# CHANNEL_DELAY.net
KiCad netlist of a schematic drawn in Altium Designer
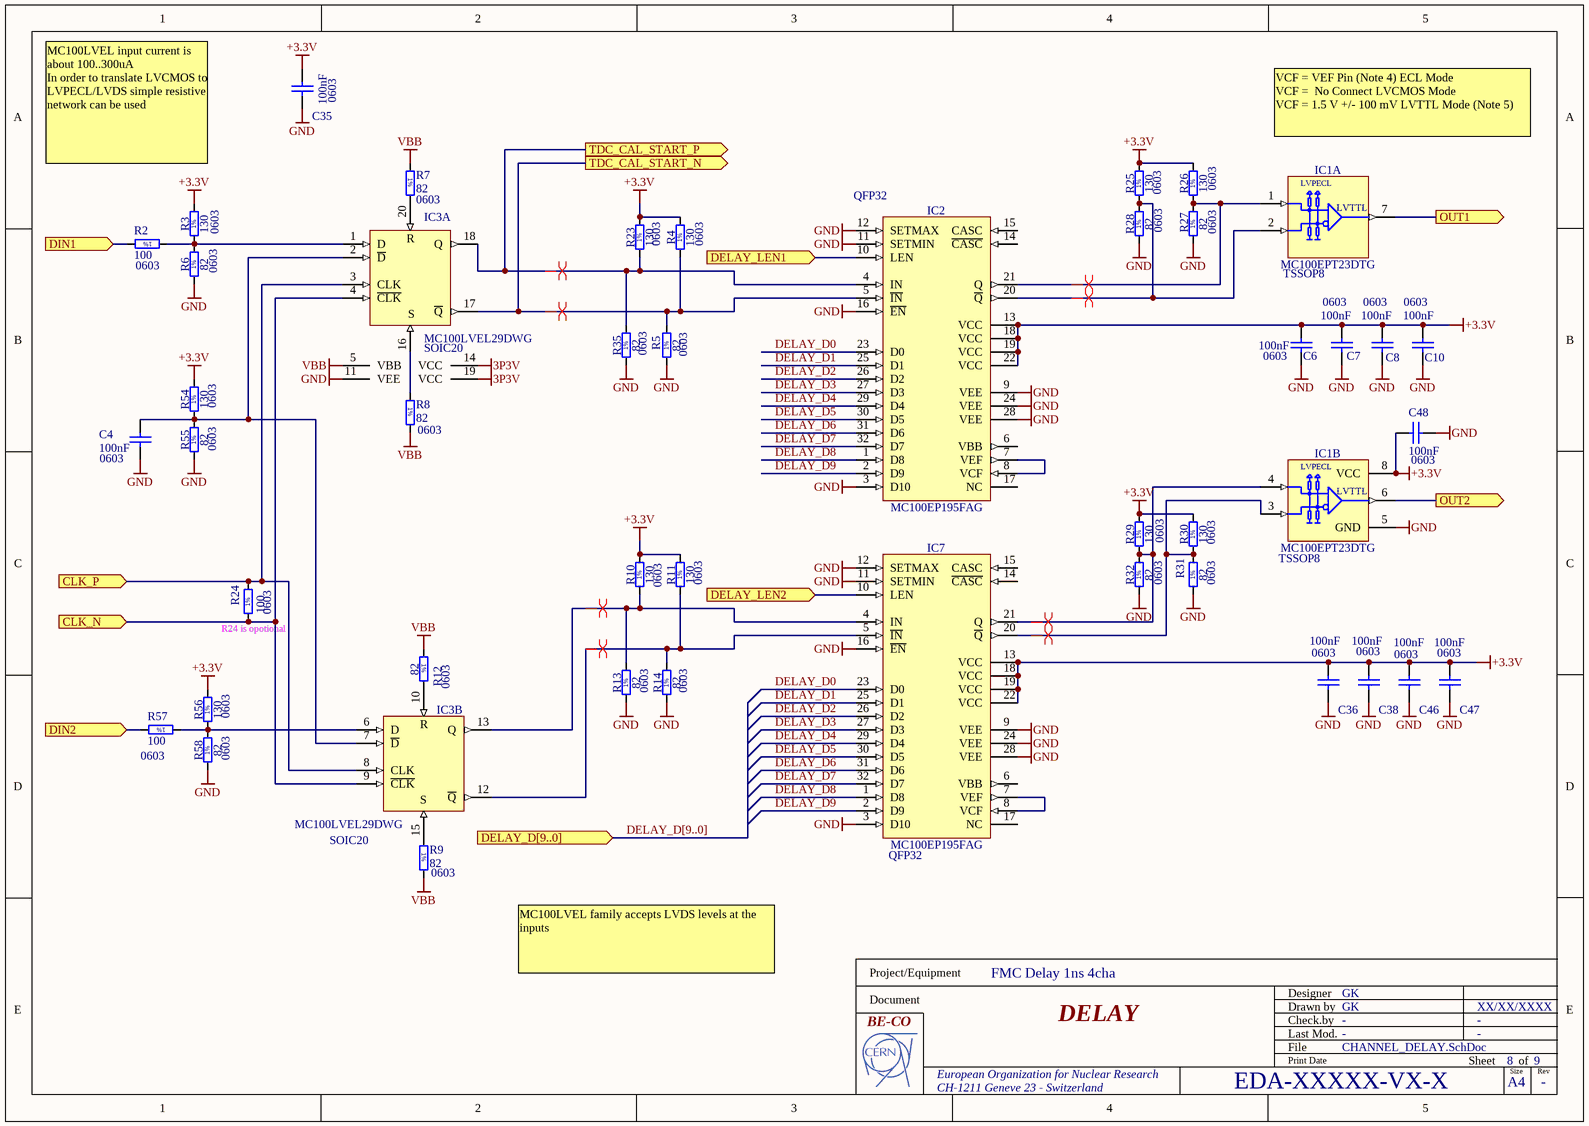
[diagram p0: CHANNEL_DELAY.SchDoc]

(export (version "E")
  (design (tool "Eeschema 10.0.6"))
  (components
    (comp (ref "C4")
      (value "100nF")
      (footprint "CAPC1608X87N")
      (description "Non-polarised capacitor")
      (fields
        (field (name "CASE") "0603")
        (field (name "MANUFACTURER1 PART NUMBER") "223858615649")
        (field (name "MANUFACTURER") "GENERIC")
        (field (name "AUTHOR") "CERN DEM JLC")
      )
      (libsource (lib "Capacitors") (part "Capacitor - non polarized"))
    )
    (comp (ref "C6")
      (value "100nF")
      (footprint "CAPC1608X87N")
      (description "Non-polarised capacitor")
      (fields
        (field (name "CASE") "0603")
        (field (name "MANUFACTURER1 PART NUMBER") "223858615649")
        (field (name "MANUFACTURER") "GENERIC")
        (field (name "AUTHOR") "CERN DEM JLC")
      )
      (libsource (lib "Capacitors") (part "Capacitor - non polarized"))
    )
    (comp (ref "C7")
      (value "100nF")
      (footprint "CAPC1608X87N")
      (description "Non-polarised capacitor")
      (fields
        (field (name "CASE") "0603")
        (field (name "MANUFACTURER1 PART NUMBER") "223858615649")
        (field (name "MANUFACTURER") "GENERIC")
        (field (name "AUTHOR") "CERN DEM JLC")
      )
      (libsource (lib "Capacitors") (part "Capacitor - non polarized"))
    )
    (comp (ref "C8")
      (value "100nF")
      (footprint "CAPC1608X87N")
      (description "Non-polarised capacitor")
      (fields
        (field (name "CASE") "0603")
        (field (name "MANUFACTURER1 PART NUMBER") "223858615649")
        (field (name "MANUFACTURER") "GENERIC")
        (field (name "AUTHOR") "CERN DEM JLC")
      )
      (libsource (lib "Capacitors") (part "Capacitor - non polarized"))
    )
    (comp (ref "C10")
      (value "100nF")
      (footprint "CAPC1608X87N")
      (description "Non-polarised capacitor")
      (fields
        (field (name "CASE") "0603")
        (field (name "MANUFACTURER1 PART NUMBER") "223858615649")
        (field (name "MANUFACTURER") "GENERIC")
        (field (name "AUTHOR") "CERN DEM JLC")
      )
      (libsource (lib "Capacitors") (part "Capacitor - non polarized"))
    )
    (comp (ref "C35")
      (value "100nF")
      (footprint "CAPC1608X87N")
      (description "Non-polarised capacitor")
      (fields
        (field (name "CASE") "0603")
        (field (name "MANUFACTURER1 PART NUMBER") "223858615649")
        (field (name "MANUFACTURER") "GENERIC")
        (field (name "AUTHOR") "CERN DEM JLC")
      )
      (libsource (lib "Capacitors") (part "Capacitor - non polarized"))
    )
    (comp (ref "C36")
      (value "100nF")
      (footprint "CAPC1608X87N")
      (description "Non-polarised capacitor")
      (fields
        (field (name "CASE") "0603")
        (field (name "MANUFACTURER1 PART NUMBER") "223858615649")
        (field (name "MANUFACTURER") "GENERIC")
        (field (name "AUTHOR") "CERN DEM JLC")
      )
      (libsource (lib "Capacitors") (part "Capacitor - non polarized"))
    )
    (comp (ref "C38")
      (value "100nF")
      (footprint "CAPC1608X87N")
      (description "Non-polarised capacitor")
      (fields
        (field (name "CASE") "0603")
        (field (name "MANUFACTURER1 PART NUMBER") "223858615649")
        (field (name "MANUFACTURER") "GENERIC")
        (field (name "AUTHOR") "CERN DEM JLC")
      )
      (libsource (lib "Capacitors") (part "Capacitor - non polarized"))
    )
    (comp (ref "C46")
      (value "100nF")
      (footprint "CAPC1608X87N")
      (description "Non-polarised capacitor")
      (fields
        (field (name "CASE") "0603")
        (field (name "MANUFACTURER1 PART NUMBER") "223858615649")
        (field (name "MANUFACTURER") "GENERIC")
        (field (name "AUTHOR") "CERN DEM JLC")
      )
      (libsource (lib "Capacitors") (part "Capacitor - non polarized"))
    )
    (comp (ref "C47")
      (value "100nF")
      (footprint "CAPC1608X87N")
      (description "Non-polarised capacitor")
      (fields
        (field (name "CASE") "0603")
        (field (name "MANUFACTURER1 PART NUMBER") "223858615649")
        (field (name "MANUFACTURER") "GENERIC")
        (field (name "AUTHOR") "CERN DEM JLC")
      )
      (libsource (lib "Capacitors") (part "Capacitor - non polarized"))
    )
    (comp (ref "C48")
      (value "100nF")
      (footprint "CAPC1608X87N")
      (description "Non-polarised capacitor")
      (fields
        (field (name "CASE") "0603")
        (field (name "MANUFACTURER1 PART NUMBER") "223858615649")
        (field (name "MANUFACTURER") "GENERIC")
        (field (name "AUTHOR") "CERN DEM JLC")
      )
      (libsource (lib "Capacitors") (part "Capacitor - non polarized"))
    )
    (comp (ref "IC1")
      (value "MC100EPT23DTG")
      (footprint "SOP65P490X110-8N")
      (description "3.3V Dual Differential LVPECL/LVDS/CML  to LVTTL/LVCMOS Translator")
      (fields
        (field (name "MANUFACTURER") "ON SEMICONDUCTOR")
        (field (name "CASE") "TSSOP8")
        (field (name "AUTHOR") "CERN DEM JLC")
      )
      (libsource (lib "ICs And Semiconductors") (part "100EPT23D"))
    )
    (comp (ref "IC2")
      (value "MC100EP195FAG")
      (footprint "QFP80P900X900X160-32AN")
      (description "3.3V ECL Programmable Delay Chip")
      (fields
        (field (name "PART NUMBER") "MC100EP195BFAG")
        (field (name "MANUFACTURER") "ON SEMICONDUCTOR")
        (field (name "CASE") "QFP32")
        (field (name "AUTHOR") "CERN DEM JLC")
      )
      (libsource (lib "ICs And Semiconductors") (part "MC100EP195FA"))
    )
    (comp (ref "IC3")
      (value "MC100LVEL29DWG")
      (footprint "SOIC127P1030X265-20N")
      (description "3.3V ECL Dual Differential Data and Clock D Flip-Flop With Set and Reset")
      (fields
        (field (name "MANUFACTURER") "ON SEMICONDUCTOR")
        (field (name "CASE") "SOIC20")
        (field (name "AUTHOR") "CERN DEM JLC")
      )
      (libsource (lib "ICs And Semiconductors") (part "100LVEL29"))
    )
    (comp (ref "IC7")
      (value "MC100EP195FAG")
      (footprint "QFP80P900X900X160-32AN")
      (description "3.3V ECL Programmable Delay Chip")
      (fields
        (field (name "PART NUMBER") "MC100EP195BFAG")
        (field (name "MANUFACTURER") "ON SEMICONDUCTOR")
        (field (name "CASE") "QFP32")
        (field (name "AUTHOR") "CERN DEM JLC")
      )
      (libsource (lib "ICs And Semiconductors") (part "MC100EP195FA"))
    )
    (comp (ref "R2")
      (value "100")
      (footprint "RESC1608X55N")
      (description "Resistor - 1%")
      (fields
        (field (name "PART NUMBER") "R0603_100R_1%_0.1W_100PPM")
        (field (name "POWER") "0.1W")
        (field (name "CASE") "0603")
        (field (name "AUTHOR") "CERN DEM JLC")
      )
      (libsource (lib "Resistors") (part "Resistor - 1%"))
    )
    (comp (ref "R3")
      (value "130")
      (footprint "RESC1608X55N")
      (description "Resistor - 1%")
      (fields
        (field (name "PART NUMBER") "R0603_130R_1%_0.1W_100PPM")
        (field (name "POWER") "0.1W")
        (field (name "CASE") "0603")
        (field (name "AUTHOR") "CERN DEM JLC")
      )
      (libsource (lib "Resistors") (part "Resistor - 1%"))
    )
    (comp (ref "R4")
      (value "130")
      (footprint "RESC1608X55N")
      (description "Resistor - 1%")
      (fields
        (field (name "PART NUMBER") "R0603_130R_1%_0.1W_100PPM")
        (field (name "POWER") "0.1W")
        (field (name "CASE") "0603")
        (field (name "AUTHOR") "CERN DEM JLC")
      )
      (libsource (lib "Resistors") (part "Resistor - 1%"))
    )
    (comp (ref "R5")
      (value "82")
      (footprint "RESC1608X55N")
      (description "Resistor - 1%")
      (fields
        (field (name "PART NUMBER") "R0603_82R_1%_0.1W_100PPM")
        (field (name "POWER") "0.1W")
        (field (name "CASE") "0603")
        (field (name "AUTHOR") "CERN DEM JLC")
      )
      (libsource (lib "Resistors") (part "Resistor - 1%"))
    )
    (comp (ref "R6")
      (value "82")
      (footprint "RESC1608X55N")
      (description "Resistor - 1%")
      (fields
        (field (name "PART NUMBER") "R0603_82R_1%_0.1W_100PPM")
        (field (name "POWER") "0.1W")
        (field (name "CASE") "0603")
        (field (name "AUTHOR") "CERN DEM JLC")
      )
      (libsource (lib "Resistors") (part "Resistor - 1%"))
    )
    (comp (ref "R7")
      (value "82")
      (footprint "RESC1608X55N")
      (description "Resistor - 1%")
      (fields
        (field (name "PART NUMBER") "R0603_82R_1%_0.1W_100PPM")
        (field (name "POWER") "0.1W")
        (field (name "CASE") "0603")
        (field (name "AUTHOR") "CERN DEM JLC")
      )
      (libsource (lib "Resistors") (part "Resistor - 1%"))
    )
    (comp (ref "R8")
      (value "82")
      (footprint "RESC1608X55N")
      (description "Resistor - 1%")
      (fields
        (field (name "PART NUMBER") "R0603_82R_1%_0.1W_100PPM")
        (field (name "POWER") "0.1W")
        (field (name "CASE") "0603")
        (field (name "AUTHOR") "CERN DEM JLC")
      )
      (libsource (lib "Resistors") (part "Resistor - 1%"))
    )
    (comp (ref "R9")
      (value "82")
      (footprint "RESC1608X55N")
      (description "Resistor - 1%")
      (fields
        (field (name "PART NUMBER") "R0603_82R_1%_0.1W_100PPM")
        (field (name "POWER") "0.1W")
        (field (name "CASE") "0603")
        (field (name "AUTHOR") "CERN DEM JLC")
      )
      (libsource (lib "Resistors") (part "Resistor - 1%"))
    )
    (comp (ref "R10")
      (value "130")
      (footprint "RESC1608X55N")
      (description "Resistor - 1%")
      (fields
        (field (name "PART NUMBER") "R0603_130R_1%_0.1W_100PPM")
        (field (name "POWER") "0.1W")
        (field (name "CASE") "0603")
        (field (name "AUTHOR") "CERN DEM JLC")
      )
      (libsource (lib "Resistors") (part "Resistor - 1%"))
    )
    (comp (ref "R11")
      (value "130")
      (footprint "RESC1608X55N")
      (description "Resistor - 1%")
      (fields
        (field (name "PART NUMBER") "R0603_130R_1%_0.1W_100PPM")
        (field (name "POWER") "0.1W")
        (field (name "CASE") "0603")
        (field (name "AUTHOR") "CERN DEM JLC")
      )
      (libsource (lib "Resistors") (part "Resistor - 1%"))
    )
    (comp (ref "R12")
      (value "82")
      (footprint "RESC1608X55N")
      (description "Resistor - 1%")
      (fields
        (field (name "PART NUMBER") "R0603_82R_1%_0.1W_100PPM")
        (field (name "POWER") "0.1W")
        (field (name "CASE") "0603")
        (field (name "AUTHOR") "CERN DEM JLC")
      )
      (libsource (lib "Resistors") (part "Resistor - 1%"))
    )
    (comp (ref "R13")
      (value "82")
      (footprint "RESC1608X55N")
      (description "Resistor - 1%")
      (fields
        (field (name "PART NUMBER") "R0603_82R_1%_0.1W_100PPM")
        (field (name "POWER") "0.1W")
        (field (name "CASE") "0603")
        (field (name "AUTHOR") "CERN DEM JLC")
      )
      (libsource (lib "Resistors") (part "Resistor - 1%"))
    )
    (comp (ref "R14")
      (value "82")
      (footprint "RESC1608X55N")
      (description "Resistor - 1%")
      (fields
        (field (name "PART NUMBER") "R0603_82R_1%_0.1W_100PPM")
        (field (name "POWER") "0.1W")
        (field (name "CASE") "0603")
        (field (name "AUTHOR") "CERN DEM JLC")
      )
      (libsource (lib "Resistors") (part "Resistor - 1%"))
    )
    (comp (ref "R23")
      (value "130")
      (footprint "RESC1608X55N")
      (description "Resistor - 1%")
      (fields
        (field (name "PART NUMBER") "R0603_130R_1%_0.1W_100PPM")
        (field (name "POWER") "0.1W")
        (field (name "CASE") "0603")
        (field (name "AUTHOR") "CERN DEM JLC")
      )
      (libsource (lib "Resistors") (part "Resistor - 1%"))
    )
    (comp (ref "R24")
      (value "100")
      (footprint "RESC1608X55N")
      (description "Resistor - 1%")
      (fields
        (field (name "PART NUMBER") "R0603_100R_1%_0.1W_100PPM")
        (field (name "POWER") "0.1W")
        (field (name "CASE") "0603")
        (field (name "AUTHOR") "CERN DEM JLC")
      )
      (libsource (lib "Resistors") (part "Resistor - 1%"))
    )
    (comp (ref "R25")
      (value "130")
      (footprint "RESC1608X55N")
      (description "Resistor - 1%")
      (fields
        (field (name "PART NUMBER") "R0603_130R_1%_0.1W_100PPM")
        (field (name "POWER") "0.1W")
        (field (name "CASE") "0603")
        (field (name "AUTHOR") "CERN DEM JLC")
      )
      (libsource (lib "Resistors") (part "Resistor - 1%"))
    )
    (comp (ref "R26")
      (value "130")
      (footprint "RESC1608X55N")
      (description "Resistor - 1%")
      (fields
        (field (name "PART NUMBER") "R0603_130R_1%_0.1W_100PPM")
        (field (name "POWER") "0.1W")
        (field (name "CASE") "0603")
        (field (name "AUTHOR") "CERN DEM JLC")
      )
      (libsource (lib "Resistors") (part "Resistor - 1%"))
    )
    (comp (ref "R27")
      (value "82")
      (footprint "RESC1608X55N")
      (description "Resistor - 1%")
      (fields
        (field (name "PART NUMBER") "R0603_82R_1%_0.1W_100PPM")
        (field (name "POWER") "0.1W")
        (field (name "CASE") "0603")
        (field (name "AUTHOR") "CERN DEM JLC")
      )
      (libsource (lib "Resistors") (part "Resistor - 1%"))
    )
    (comp (ref "R28")
      (value "82")
      (footprint "RESC1608X55N")
      (description "Resistor - 1%")
      (fields
        (field (name "PART NUMBER") "R0603_82R_1%_0.1W_100PPM")
        (field (name "POWER") "0.1W")
        (field (name "CASE") "0603")
        (field (name "AUTHOR") "CERN DEM JLC")
      )
      (libsource (lib "Resistors") (part "Resistor - 1%"))
    )
    (comp (ref "R29")
      (value "130")
      (footprint "RESC1608X55N")
      (description "Resistor - 1%")
      (fields
        (field (name "PART NUMBER") "R0603_130R_1%_0.1W_100PPM")
        (field (name "POWER") "0.1W")
        (field (name "CASE") "0603")
        (field (name "AUTHOR") "CERN DEM JLC")
      )
      (libsource (lib "Resistors") (part "Resistor - 1%"))
    )
    (comp (ref "R30")
      (value "130")
      (footprint "RESC1608X55N")
      (description "Resistor - 1%")
      (fields
        (field (name "PART NUMBER") "R0603_130R_1%_0.1W_100PPM")
        (field (name "POWER") "0.1W")
        (field (name "CASE") "0603")
        (field (name "AUTHOR") "CERN DEM JLC")
      )
      (libsource (lib "Resistors") (part "Resistor - 1%"))
    )
    (comp (ref "R31")
      (value "82")
      (footprint "RESC1608X55N")
      (description "Resistor - 1%")
      (fields
        (field (name "PART NUMBER") "R0603_82R_1%_0.1W_100PPM")
        (field (name "POWER") "0.1W")
        (field (name "CASE") "0603")
        (field (name "AUTHOR") "CERN DEM JLC")
      )
      (libsource (lib "Resistors") (part "Resistor - 1%"))
    )
    (comp (ref "R32")
      (value "82")
      (footprint "RESC1608X55N")
      (description "Resistor - 1%")
      (fields
        (field (name "PART NUMBER") "R0603_82R_1%_0.1W_100PPM")
        (field (name "POWER") "0.1W")
        (field (name "CASE") "0603")
        (field (name "AUTHOR") "CERN DEM JLC")
      )
      (libsource (lib "Resistors") (part "Resistor - 1%"))
    )
    (comp (ref "R35")
      (value "82")
      (footprint "RESC1608X55N")
      (description "Resistor - 1%")
      (fields
        (field (name "PART NUMBER") "R0603_82R_1%_0.1W_100PPM")
        (field (name "POWER") "0.1W")
        (field (name "CASE") "0603")
        (field (name "AUTHOR") "CERN DEM JLC")
      )
      (libsource (lib "Resistors") (part "Resistor - 1%"))
    )
    (comp (ref "R54")
      (value "130")
      (footprint "RESC1608X55N")
      (description "Resistor - 1%")
      (fields
        (field (name "PART NUMBER") "R0603_130R_1%_0.1W_100PPM")
        (field (name "POWER") "0.1W")
        (field (name "CASE") "0603")
        (field (name "AUTHOR") "CERN DEM JLC")
      )
      (libsource (lib "Resistors") (part "Resistor - 1%"))
    )
    (comp (ref "R55")
      (value "82")
      (footprint "RESC1608X55N")
      (description "Resistor - 1%")
      (fields
        (field (name "PART NUMBER") "R0603_82R_1%_0.1W_100PPM")
        (field (name "POWER") "0.1W")
        (field (name "CASE") "0603")
        (field (name "AUTHOR") "CERN DEM JLC")
      )
      (libsource (lib "Resistors") (part "Resistor - 1%"))
    )
    (comp (ref "R56")
      (value "130")
      (footprint "RESC1608X55N")
      (description "Resistor - 1%")
      (fields
        (field (name "PART NUMBER") "R0603_130R_1%_0.1W_100PPM")
        (field (name "POWER") "0.1W")
        (field (name "CASE") "0603")
        (field (name "AUTHOR") "CERN DEM JLC")
      )
      (libsource (lib "Resistors") (part "Resistor - 1%"))
    )
    (comp (ref "R57")
      (value "100")
      (footprint "RESC1608X55N")
      (description "Resistor - 1%")
      (fields
        (field (name "PART NUMBER") "R0603_100R_1%_0.1W_100PPM")
        (field (name "POWER") "0.1W")
        (field (name "CASE") "0603")
        (field (name "AUTHOR") "CERN DEM JLC")
      )
      (libsource (lib "Resistors") (part "Resistor - 1%"))
    )
    (comp (ref "R58")
      (value "82")
      (footprint "RESC1608X55N")
      (description "Resistor - 1%")
      (fields
        (field (name "PART NUMBER") "R0603_82R_1%_0.1W_100PPM")
        (field (name "POWER") "0.1W")
        (field (name "CASE") "0603")
        (field (name "AUTHOR") "CERN DEM JLC")
      )
      (libsource (lib "Resistors") (part "Resistor - 1%"))
    )
  )
  (nets
    (net (code "1") (name "+3.3V") (class "Default")
      (node (ref "C10") (pin "1") (pinfunction "1_1") (pintype "passive"))
      (node (ref "C35") (pin "1") (pinfunction "1_1") (pintype "passive"))
      (node (ref "C36") (pin "1") (pinfunction "1_1") (pintype "passive"))
      (node (ref "C38") (pin "1") (pinfunction "1_1") (pintype "passive"))
      (node (ref "C46") (pin "1") (pinfunction "1_1") (pintype "passive"))
      (node (ref "C47") (pin "1") (pinfunction "1_1") (pintype "passive"))
      (node (ref "C48") (pin "1") (pinfunction "1_1") (pintype "passive"))
      (node (ref "C6") (pin "1") (pinfunction "1_1") (pintype "passive"))
      (node (ref "C7") (pin "1") (pinfunction "1_1") (pintype "passive"))
      (node (ref "C8") (pin "1") (pinfunction "1_1") (pintype "passive"))
      (node (ref "IC1") (pin "8") (pinfunction "VCC_8") (pintype "power_in"))
      (node (ref "IC2") (pin "13") (pinfunction "VCC_13") (pintype "power_in"))
      (node (ref "IC2") (pin "18") (pinfunction "VCC_18") (pintype "power_in"))
      (node (ref "IC2") (pin "19") (pinfunction "VCC_19") (pintype "power_in"))
      (node (ref "IC2") (pin "22") (pinfunction "VCC_22") (pintype "power_in"))
      (node (ref "IC3") (pin "14") (pinfunction "VCC_14") (pintype "power_in"))
      (node (ref "IC3") (pin "19") (pinfunction "VCC_19") (pintype "power_in"))
      (node (ref "IC7") (pin "13") (pinfunction "VCC_13") (pintype "power_in"))
      (node (ref "IC7") (pin "18") (pinfunction "VCC_18") (pintype "power_in"))
      (node (ref "IC7") (pin "19") (pinfunction "VCC_19") (pintype "power_in"))
      (node (ref "IC7") (pin "22") (pinfunction "VCC_22") (pintype "power_in"))
      (node (ref "R10") (pin "2") (pinfunction "2_2") (pintype "passive"))
      (node (ref "R11") (pin "2") (pinfunction "2_2") (pintype "passive"))
      (node (ref "R23") (pin "2") (pinfunction "2_2") (pintype "passive"))
      (node (ref "R25") (pin "2") (pinfunction "2_2") (pintype "passive"))
      (node (ref "R26") (pin "2") (pinfunction "2_2") (pintype "passive"))
      (node (ref "R29") (pin "2") (pinfunction "2_2") (pintype "passive"))
      (node (ref "R3") (pin "2") (pinfunction "2_2") (pintype "passive"))
      (node (ref "R30") (pin "2") (pinfunction "2_2") (pintype "passive"))
      (node (ref "R4") (pin "2") (pinfunction "2_2") (pintype "passive"))
      (node (ref "R54") (pin "2") (pinfunction "2_2") (pintype "passive"))
      (node (ref "R56") (pin "2") (pinfunction "2_2") (pintype "passive"))
    )
    (net (code "2") (name "/CLK_N") (class "Default")
      (node (ref "IC3") (pin "4") (pinfunction "~{CLK}_4") (pintype "input"))
      (node (ref "IC3") (pin "9") (pinfunction "~{CLK}_9") (pintype "input"))
      (node (ref "R24") (pin "1") (pinfunction "1_1") (pintype "passive"))
    )
    (net (code "3") (name "/CLK_P") (class "Default")
      (node (ref "IC3") (pin "3") (pinfunction "CLK_3") (pintype "input"))
      (node (ref "IC3") (pin "8") (pinfunction "CLK_8") (pintype "input"))
      (node (ref "R24") (pin "2") (pinfunction "2_2") (pintype "passive"))
    )
    (net (code "4") (name "/DELAY_D0") (class "Default")
      (node (ref "IC2") (pin "23") (pinfunction "D0_23") (pintype "input"))
      (node (ref "IC7") (pin "23") (pinfunction "D0_23") (pintype "input"))
    )
    (net (code "5") (name "/DELAY_D1") (class "Default")
      (node (ref "IC2") (pin "25") (pinfunction "D1_25") (pintype "input"))
      (node (ref "IC7") (pin "25") (pinfunction "D1_25") (pintype "input"))
    )
    (net (code "6") (name "/DELAY_D2") (class "Default")
      (node (ref "IC2") (pin "26") (pinfunction "D2_26") (pintype "input"))
      (node (ref "IC7") (pin "26") (pinfunction "D2_26") (pintype "input"))
    )
    (net (code "7") (name "/DELAY_D3") (class "Default")
      (node (ref "IC2") (pin "27") (pinfunction "D3_27") (pintype "input"))
      (node (ref "IC7") (pin "27") (pinfunction "D3_27") (pintype "input"))
    )
    (net (code "8") (name "/DELAY_D4") (class "Default")
      (node (ref "IC2") (pin "29") (pinfunction "D4_29") (pintype "input"))
      (node (ref "IC7") (pin "29") (pinfunction "D4_29") (pintype "input"))
    )
    (net (code "9") (name "/DELAY_D5") (class "Default")
      (node (ref "IC2") (pin "30") (pinfunction "D5_30") (pintype "input"))
      (node (ref "IC7") (pin "30") (pinfunction "D5_30") (pintype "input"))
    )
    (net (code "10") (name "/DELAY_D6") (class "Default")
      (node (ref "IC2") (pin "31") (pinfunction "D6_31") (pintype "input"))
      (node (ref "IC7") (pin "31") (pinfunction "D6_31") (pintype "input"))
    )
    (net (code "11") (name "/DELAY_D7") (class "Default")
      (node (ref "IC2") (pin "32") (pinfunction "D7_32") (pintype "input"))
      (node (ref "IC7") (pin "32") (pinfunction "D7_32") (pintype "input"))
    )
    (net (code "12") (name "/DELAY_D8") (class "Default")
      (node (ref "IC2") (pin "1") (pinfunction "D8_1") (pintype "input"))
      (node (ref "IC7") (pin "1") (pinfunction "D8_1") (pintype "input"))
    )
    (net (code "13") (name "/DELAY_D9") (class "Default")
      (node (ref "IC2") (pin "2") (pinfunction "D9_2") (pintype "input"))
      (node (ref "IC7") (pin "2") (pinfunction "D9_2") (pintype "input"))
    )
    (net (code "15") (name "/DELAY_LEN1") (class "Default")
      (node (ref "IC2") (pin "10") (pinfunction "LEN_10") (pintype "input"))
    )
    (net (code "16") (name "/DELAY_LEN2") (class "Default")
      (node (ref "IC7") (pin "10") (pinfunction "LEN_10") (pintype "input"))
    )
    (net (code "17") (name "/DIN1") (class "Default")
      (node (ref "R2") (pin "2") (pinfunction "2_2") (pintype "passive"))
    )
    (net (code "18") (name "/DIN2") (class "Default")
      (node (ref "R57") (pin "2") (pinfunction "2_2") (pintype "passive"))
    )
    (net (code "19") (name "/OUT1") (class "Default")
      (node (ref "IC1") (pin "7") (pinfunction "Q0_7") (pintype "output"))
    )
    (net (code "20") (name "/OUT2") (class "Default")
      (node (ref "IC1") (pin "6") (pinfunction "Q0_6") (pintype "output"))
    )
    (net (code "21") (name "/TDC_CAL_START_N") (class "Default")
      (node (ref "IC2") (pin "5") (pinfunction "~{IN}_5") (pintype "input"))
      (node (ref "IC3") (pin "17") (pinfunction "~{Q}_17") (pintype "output"))
      (node (ref "R4") (pin "1") (pinfunction "1_1") (pintype "passive"))
      (node (ref "R5") (pin "2") (pinfunction "2_2") (pintype "passive"))
    )
    (net (code "22") (name "/TDC_CAL_START_P") (class "Default")
      (node (ref "IC2") (pin "4") (pinfunction "IN_4") (pintype "input"))
      (node (ref "IC3") (pin "18") (pinfunction "Q_18") (pintype "output"))
      (node (ref "R23") (pin "1") (pinfunction "1_1") (pintype "passive"))
      (node (ref "R35") (pin "2") (pinfunction "2_2") (pintype "passive"))
    )
    (net (code "23") (name "GND") (class "Default")
      (node (ref "C10") (pin "2") (pinfunction "2_2") (pintype "passive"))
      (node (ref "C35") (pin "2") (pinfunction "2_2") (pintype "passive"))
      (node (ref "C36") (pin "2") (pinfunction "2_2") (pintype "passive"))
      (node (ref "C38") (pin "2") (pinfunction "2_2") (pintype "passive"))
      (node (ref "C4") (pin "2") (pinfunction "2_2") (pintype "passive"))
      (node (ref "C46") (pin "2") (pinfunction "2_2") (pintype "passive"))
      (node (ref "C47") (pin "2") (pinfunction "2_2") (pintype "passive"))
      (node (ref "C48") (pin "2") (pinfunction "2_2") (pintype "passive"))
      (node (ref "C6") (pin "2") (pinfunction "2_2") (pintype "passive"))
      (node (ref "C7") (pin "2") (pinfunction "2_2") (pintype "passive"))
      (node (ref "C8") (pin "2") (pinfunction "2_2") (pintype "passive"))
      (node (ref "IC1") (pin "5") (pinfunction "GND_5") (pintype "power_in"))
      (node (ref "IC2") (pin "11") (pinfunction "SETMIN_11") (pintype "input"))
      (node (ref "IC2") (pin "12") (pinfunction "SETMAX_12") (pintype "input"))
      (node (ref "IC2") (pin "16") (pinfunction "~{EN}_16") (pintype "input"))
      (node (ref "IC2") (pin "24") (pinfunction "VEE_24") (pintype "power_in"))
      (node (ref "IC2") (pin "28") (pinfunction "VEE_28") (pintype "power_in"))
      (node (ref "IC2") (pin "3") (pinfunction "D10_3") (pintype "input"))
      (node (ref "IC2") (pin "9") (pinfunction "VEE_9") (pintype "power_in"))
      (node (ref "IC3") (pin "11") (pinfunction "VEE_11") (pintype "power_in"))
      (node (ref "IC7") (pin "11") (pinfunction "SETMIN_11") (pintype "input"))
      (node (ref "IC7") (pin "12") (pinfunction "SETMAX_12") (pintype "input"))
      (node (ref "IC7") (pin "16") (pinfunction "~{EN}_16") (pintype "input"))
      (node (ref "IC7") (pin "24") (pinfunction "VEE_24") (pintype "power_in"))
      (node (ref "IC7") (pin "28") (pinfunction "VEE_28") (pintype "power_in"))
      (node (ref "IC7") (pin "3") (pinfunction "D10_3") (pintype "input"))
      (node (ref "IC7") (pin "9") (pinfunction "VEE_9") (pintype "power_in"))
      (node (ref "R13") (pin "1") (pinfunction "1_1") (pintype "passive"))
      (node (ref "R14") (pin "1") (pinfunction "1_1") (pintype "passive"))
      (node (ref "R27") (pin "1") (pinfunction "1_1") (pintype "passive"))
      (node (ref "R28") (pin "1") (pinfunction "1_1") (pintype "passive"))
      (node (ref "R31") (pin "1") (pinfunction "1_1") (pintype "passive"))
      (node (ref "R32") (pin "1") (pinfunction "1_1") (pintype "passive"))
      (node (ref "R35") (pin "1") (pinfunction "1_1") (pintype "passive"))
      (node (ref "R5") (pin "1") (pinfunction "1_1") (pintype "passive"))
      (node (ref "R55") (pin "1") (pinfunction "1_1") (pintype "passive"))
      (node (ref "R58") (pin "1") (pinfunction "1_1") (pintype "passive"))
      (node (ref "R6") (pin "1") (pinfunction "1_1") (pintype "passive"))
    )
    (net (code "24") (name "Net-(IC1A-D0)") (class "Default")
      (node (ref "IC1") (pin "1") (pinfunction "D0_1") (pintype "input"))
      (node (ref "IC2") (pin "21") (pinfunction "Q_21") (pintype "output"))
      (node (ref "R26") (pin "1") (pinfunction "1_1") (pintype "passive"))
      (node (ref "R27") (pin "2") (pinfunction "2_2") (pintype "passive"))
    )
    (net (code "25") (name "Net-(IC1A-~{D0})") (class "Default")
      (node (ref "IC1") (pin "2") (pinfunction "~{D0}_2") (pintype "input"))
      (node (ref "IC2") (pin "20") (pinfunction "~{Q}_20") (pintype "output"))
      (node (ref "R25") (pin "1") (pinfunction "1_1") (pintype "passive"))
      (node (ref "R28") (pin "2") (pinfunction "2_2") (pintype "passive"))
    )
    (net (code "26") (name "Net-(IC1B-D0)") (class "Default")
      (node (ref "IC1") (pin "4") (pinfunction "D0_4") (pintype "input"))
      (node (ref "IC7") (pin "21") (pinfunction "Q_21") (pintype "output"))
      (node (ref "R29") (pin "1") (pinfunction "1_1") (pintype "passive"))
      (node (ref "R32") (pin "2") (pinfunction "2_2") (pintype "passive"))
    )
    (net (code "27") (name "Net-(IC1B-~{D0})") (class "Default")
      (node (ref "IC1") (pin "3") (pinfunction "~{D0}_3") (pintype "input"))
      (node (ref "IC7") (pin "20") (pinfunction "~{Q}_20") (pintype "output"))
      (node (ref "R30") (pin "1") (pinfunction "1_1") (pintype "passive"))
      (node (ref "R31") (pin "2") (pinfunction "2_2") (pintype "passive"))
    )
    (net (code "28") (name "Net-(IC2-VCF)") (class "Default")
      (node (ref "IC2") (pin "7") (pinfunction "VEF_7") (pintype "output"))
      (node (ref "IC2") (pin "8") (pinfunction "VCF_8") (pintype "input"))
    )
    (net (code "29") (name "Net-(IC3A-D)") (class "Default")
      (node (ref "IC3") (pin "1") (pinfunction "D_1") (pintype "input"))
      (node (ref "R2") (pin "1") (pinfunction "1_1") (pintype "passive"))
      (node (ref "R3") (pin "1") (pinfunction "1_1") (pintype "passive"))
      (node (ref "R6") (pin "2") (pinfunction "2_2") (pintype "passive"))
    )
    (net (code "30") (name "Net-(IC3A-R)") (class "Default")
      (node (ref "IC3") (pin "20") (pinfunction "R_20") (pintype "input"))
      (node (ref "R7") (pin "2") (pinfunction "2_2") (pintype "passive"))
    )
    (net (code "31") (name "Net-(IC3A-S)") (class "Default")
      (node (ref "IC3") (pin "16") (pinfunction "S_16") (pintype "input"))
      (node (ref "R8") (pin "1") (pinfunction "1_1") (pintype "passive"))
    )
    (net (code "32") (name "Net-(IC3A-~{D})") (class "Default")
      (node (ref "C4") (pin "1") (pinfunction "1_1") (pintype "passive"))
      (node (ref "IC3") (pin "2") (pinfunction "~{D}_2") (pintype "input"))
      (node (ref "IC3") (pin "7") (pinfunction "~{D}_7") (pintype "input"))
      (node (ref "R54") (pin "1") (pinfunction "1_1") (pintype "passive"))
      (node (ref "R55") (pin "2") (pinfunction "2_2") (pintype "passive"))
    )
    (net (code "33") (name "Net-(IC3B-D)") (class "Default")
      (node (ref "IC3") (pin "6") (pinfunction "D_6") (pintype "input"))
      (node (ref "R56") (pin "1") (pinfunction "1_1") (pintype "passive"))
      (node (ref "R57") (pin "1") (pinfunction "1_1") (pintype "passive"))
      (node (ref "R58") (pin "2") (pinfunction "2_2") (pintype "passive"))
    )
    (net (code "34") (name "Net-(IC3B-Q)") (class "Default")
      (node (ref "IC3") (pin "13") (pinfunction "Q_13") (pintype "output"))
      (node (ref "IC7") (pin "4") (pinfunction "IN_4") (pintype "input"))
      (node (ref "R10") (pin "1") (pinfunction "1_1") (pintype "passive"))
      (node (ref "R13") (pin "2") (pinfunction "2_2") (pintype "passive"))
    )
    (net (code "35") (name "Net-(IC3B-R)") (class "Default")
      (node (ref "IC3") (pin "10") (pinfunction "R_10") (pintype "input"))
      (node (ref "R12") (pin "2") (pinfunction "2_2") (pintype "passive"))
    )
    (net (code "36") (name "Net-(IC3B-S)") (class "Default")
      (node (ref "IC3") (pin "15") (pinfunction "S_15") (pintype "input"))
      (node (ref "R9") (pin "1") (pinfunction "1_1") (pintype "passive"))
    )
    (net (code "37") (name "Net-(IC3B-~{Q})") (class "Default")
      (node (ref "IC3") (pin "12") (pinfunction "~{Q}_12") (pintype "output"))
      (node (ref "IC7") (pin "5") (pinfunction "~{IN}_5") (pintype "input"))
      (node (ref "R11") (pin "1") (pinfunction "1_1") (pintype "passive"))
      (node (ref "R14") (pin "2") (pinfunction "2_2") (pintype "passive"))
    )
    (net (code "38") (name "Net-(IC7-VCF)") (class "Default")
      (node (ref "IC7") (pin "7") (pinfunction "VEF_7") (pintype "output"))
      (node (ref "IC7") (pin "8") (pinfunction "VCF_8") (pintype "input"))
    )
    (net (code "39") (name "VBB") (class "Default")
      (node (ref "IC3") (pin "5") (pinfunction "VBB_5") (pintype "power_in"))
      (node (ref "R12") (pin "1") (pinfunction "1_1") (pintype "passive"))
      (node (ref "R7") (pin "1") (pinfunction "1_1") (pintype "passive"))
      (node (ref "R8") (pin "2") (pinfunction "2_2") (pintype "passive"))
      (node (ref "R9") (pin "2") (pinfunction "2_2") (pintype "passive"))
    )
    (net (code "40") (name "unconnected-(IC2-CASC-Pad15)") (class "Default")
      (node (ref "IC2") (pin "15") (pinfunction "CASC_15") (pintype "input"))
    )
    (net (code "41") (name "unconnected-(IC2-NC-Pad17)") (class "Default")
      (node (ref "IC2") (pin "17") (pinfunction "NC_17") (pintype "passive"))
    )
    (net (code "42") (name "unconnected-(IC2-VBB-Pad6)") (class "Default")
      (node (ref "IC2") (pin "6") (pinfunction "VBB_6") (pintype "output"))
    )
    (net (code "43") (name "unconnected-(IC2-~{CASC}-Pad14)") (class "Default")
      (node (ref "IC2") (pin "14") (pinfunction "~{CASC}_14") (pintype "input"))
    )
    (net (code "44") (name "unconnected-(IC7-CASC-Pad15)") (class "Default")
      (node (ref "IC7") (pin "15") (pinfunction "CASC_15") (pintype "input"))
    )
    (net (code "45") (name "unconnected-(IC7-NC-Pad17)") (class "Default")
      (node (ref "IC7") (pin "17") (pinfunction "NC_17") (pintype "passive"))
    )
    (net (code "46") (name "unconnected-(IC7-VBB-Pad6)") (class "Default")
      (node (ref "IC7") (pin "6") (pinfunction "VBB_6") (pintype "output"))
    )
    (net (code "47") (name "unconnected-(IC7-~{CASC}-Pad14)") (class "Default")
      (node (ref "IC7") (pin "14") (pinfunction "~{CASC}_14") (pintype "input"))
    )
  )
)
